# AT_LINK.net
KiCad netlist of a schematic drawn in Altium Designer
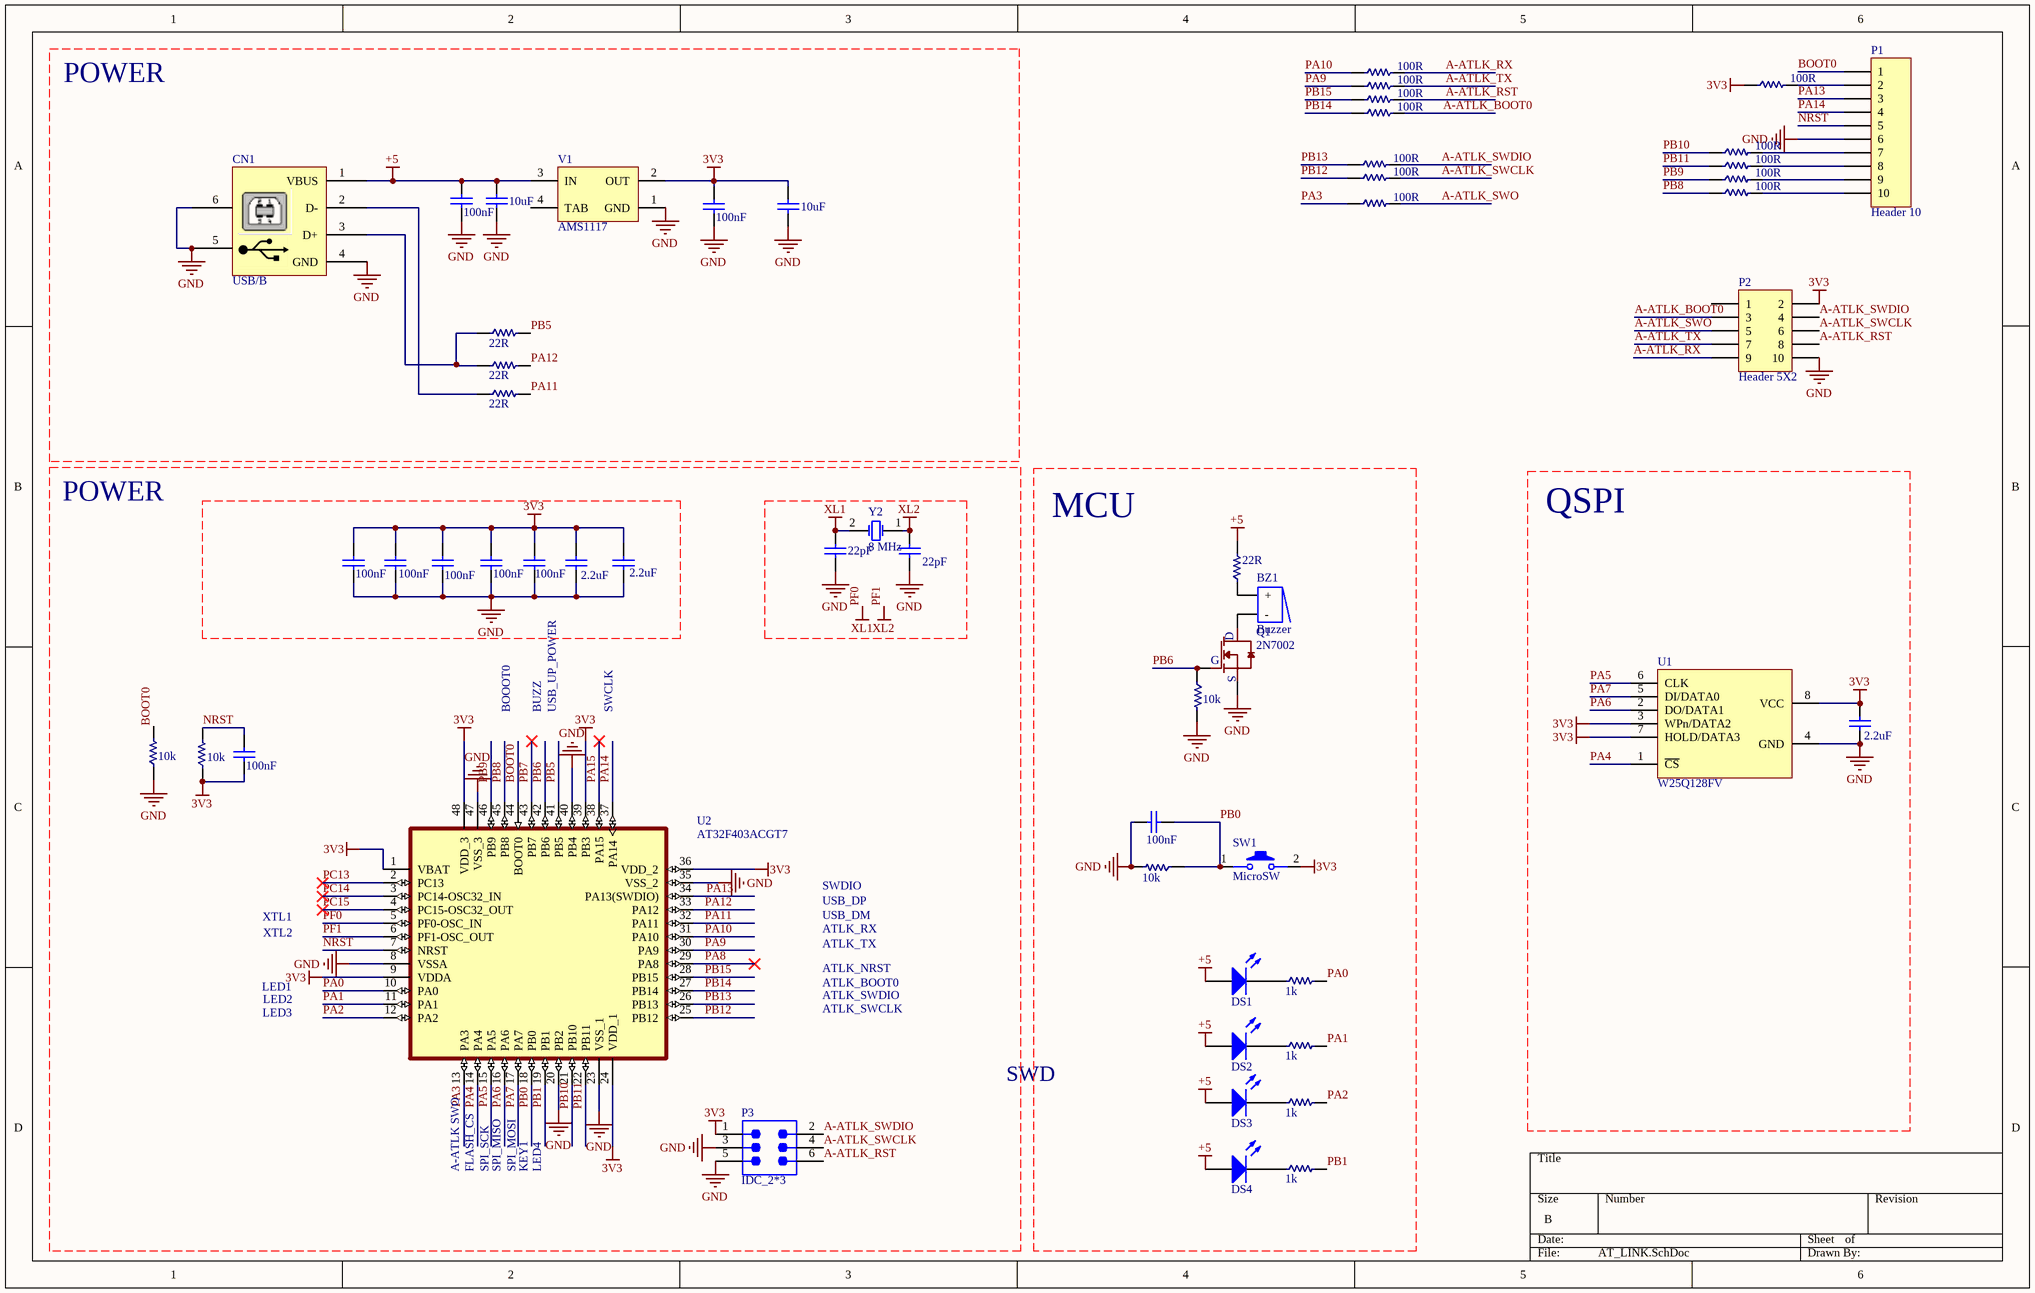
[diagram p0: AT_LINK.SchDoc]

(export (version "E")
  (design (tool "Eeschema 10.0.6"))
  (components
    (comp (ref "BZ1")
      (value "Buzzer")
      (footprint "Buzzer 3M")
      (fields (field (name "PART") "BUZZER 5V") (field (name "POWER") "CHINA"))
      (libsource (lib "NKH_Contacts") (part "Buzzer_small"))
    )
    (comp (ref "C1")
      (value "100nF")
      (footprint "CAP 0603")
      (description "cap_no_polar_seramic_multilayer")
      (fields (field (name "PART") "Cap-smd-0603-100nf"))
      (libsource (lib "R_C_D_T") (part "cap_no_polar_sig"))
    )
    (comp (ref "C2")
      (value "10uF")
      (footprint "CAP1206")
      (description "cap_no_polar_seramic_multilayer")
      (fields (field (name "PART") "Cap-smd-1206-10uf"))
      (libsource (lib "R_C_D_T") (part "cap_no_polar_sig"))
    )
    (comp (ref "C3")
      (value "100nF")
      (footprint "CAP 0603")
      (description "cap_no_polar_seramic_multilayer")
      (fields (field (name "PART") "Cap-smd-0603-100nf"))
      (libsource (lib "R_C_D_T") (part "cap_no_polar_sig"))
    )
    (comp (ref "C4")
      (value "10uF")
      (footprint "CAP1206")
      (description "cap_no_polar_seramic_multilayer")
      (fields (field (name "PART") "Cap-smd-1206-10uf"))
      (libsource (lib "R_C_D_T") (part "cap_no_polar_sig"))
    )
    (comp (ref "C5")
      (value "22pF")
      (footprint "CAP 0603")
      (description "cap_no_polar_seramic_multilayer")
      (fields (field (name "PART") "Cap-smd-0603-22pf"))
      (libsource (lib "R_C_D_T") (part "cap_no_polar_sig"))
    )
    (comp (ref "C6")
      (value "100nF")
      (footprint "CAP 0603")
      (description "cap_no_polar_seramic_multilayer")
      (fields (field (name "PART") "Cap-smd-0603-100nf"))
      (libsource (lib "R_C_D_T") (part "cap_no_polar_sig"))
    )
    (comp (ref "C7")
      (value "2.2uF")
      (footprint "CAP 0603")
      (description "cap_no_polar_seramic_multilayer")
      (fields (field (name "PART") "Cap-smd-0603-2.2uf"))
      (libsource (lib "R_C_D_T") (part "cap_no_polar_sig"))
    )
    (comp (ref "C8")
      (value "22pF")
      (footprint "CAP 0603")
      (description "cap_no_polar_seramic_multilayer")
      (fields (field (name "PART") "Cap-smd-0603-22pf"))
      (libsource (lib "R_C_D_T") (part "cap_no_polar_sig"))
    )
    (comp (ref "C9")
      (value "100nF")
      (footprint "CAP 0603")
      (description "cap_no_polar_seramic_multilayer")
      (fields (field (name "PART") "Cap-smd-0603-100nf"))
      (libsource (lib "R_C_D_T") (part "cap_no_polar_sig"))
    )
    (comp (ref "C10")
      (value "100nF")
      (footprint "CAP 0603")
      (description "cap_no_polar_seramic_multilayer")
      (fields (field (name "PART") "Cap-smd-0603-100nf"))
      (libsource (lib "R_C_D_T") (part "cap_no_polar_sig"))
    )
    (comp (ref "C11")
      (value "100nF")
      (footprint "CAP 0603")
      (description "cap_no_polar_seramic_multilayer")
      (fields (field (name "PART") "Cap-smd-0603-100nf"))
      (libsource (lib "R_C_D_T") (part "cap_no_polar_sig"))
    )
    (comp (ref "C12")
      (value "100nF")
      (footprint "CAP 0603")
      (description "cap_no_polar_seramic_multilayer")
      (fields (field (name "PART") "Cap-smd-0603-100nf"))
      (libsource (lib "R_C_D_T") (part "cap_no_polar_sig"))
    )
    (comp (ref "C13")
      (value "2.2uF")
      (footprint "CAP 0603")
      (description "cap_no_polar_seramic_multilayer")
      (fields (field (name "PART") "Cap-smd-0603-2.2uf"))
      (libsource (lib "R_C_D_T") (part "cap_no_polar_sig"))
    )
    (comp (ref "C14")
      (value "2.2uF")
      (footprint "CAP 0603")
      (description "cap_no_polar_seramic_multilayer")
      (fields (field (name "PART") "Cap-smd-0603-2.2uf"))
      (libsource (lib "R_C_D_T") (part "cap_no_polar_sig"))
    )
    (comp (ref "C15")
      (value "100nF")
      (footprint "CAP 0603")
      (description "cap_no_polar_seramic_multilayer")
      (fields (field (name "PART") "Cap-smd-0603-100nf"))
      (libsource (lib "R_C_D_T") (part "cap_no_polar_sig"))
    )
    (comp (ref "C16")
      (value "100nF")
      (footprint "CAP 0603")
      (description "cap_no_polar_seramic_multilayer")
      (fields (field (name "PART") "Cap-smd-0603-100nf"))
      (libsource (lib "R_C_D_T") (part "cap_no_polar_sig"))
    )
    (comp (ref "CN1")
      (value "USB/B")
      (footprint "USB_B")
      (description "USB Connector-B Type")
      (fields
        (field (name "PART") "USB_B")
        (field (name "POWER") "CHINA")
        (field (name "DESIGNER") "Eng. Saeid Jorablo")
      )
      (libsource (lib "NKH_Contacts") (part "USB_B"))
    )
    (comp (ref "DS1")
      (value "75 mW & 20 mA")
      (footprint "LED 0805 SMD")
      (fields (field (name "PART") "LED_0805_Red"))
      (libsource (lib "R_C_D_T") (part "LED"))
    )
    (comp (ref "DS2")
      (value "75 mW & 20 mA")
      (footprint "LED 0805 SMD")
      (fields (field (name "PART") "LED_0805_Red"))
      (libsource (lib "R_C_D_T") (part "LED"))
    )
    (comp (ref "DS3")
      (value "75 mW & 20 mA")
      (footprint "LED 0805 SMD")
      (fields (field (name "PART") "LED_0805_Red"))
      (libsource (lib "R_C_D_T") (part "LED"))
    )
    (comp (ref "DS4")
      (value "75 mW & 20 mA")
      (footprint "LED 0805 SMD")
      (fields (field (name "PART") "LED_0805_Red"))
      (libsource (lib "R_C_D_T") (part "LED"))
    )
    (comp (ref "P1")
      (value "Header 10")
      (footprint "HDR1X10")
      (description "Header, 10-Pin")
      (fields (field (name "PUBLISHER") "Altium Limited"))
      (libsource (lib "Miscellaneous Connectors") (part "Header 10"))
    )
    (comp (ref "P2")
      (value "Header 5X2")
      (footprint "HDR2X5")
      (description "Header, 5-Pin, Dual row")
      (fields (field (name "PUBLISHER") "Altium Limited"))
      (libsource (lib "Miscellaneous Connectors") (part "Header 5X2"))
    )
    (comp (ref "P3")
      (value "IDC_2*3")
      (footprint "HDB-6 right")
      (fields (field (name "PART") "HDB-2*3 Right"))
      (libsource (lib "NKH_Contacts") (part "IDC_2*3"))
    )
    (comp (ref "Q1")
      (value "2N7002")
      (footprint "SOT23_BEC_M")
      (fields (field (name "PART") "Mosfet-n-channel-2n7002"))
      (libsource (lib "R_C_D_T") (part "2N7002"))
    )
    (comp (ref "res1")
      (value "100R")
      (footprint "RES1206")
      (fields (field (name "PART") "resistor-smd-1206-100R") (field (name "DESIGNER") "rashid_behdarvand"))
      (libsource (lib "R_C_D_T") (part "resistor"))
    )
    (comp (ref "res2")
      (value "100R")
      (footprint "RES1206")
      (fields (field (name "PART") "resistor-smd-1206-100R") (field (name "DESIGNER") "rashid_behdarvand"))
      (libsource (lib "R_C_D_T") (part "resistor"))
    )
    (comp (ref "res3")
      (value "100R")
      (footprint "RES1206")
      (fields (field (name "PART") "resistor-smd-1206-100R") (field (name "DESIGNER") "rashid_behdarvand"))
      (libsource (lib "R_C_D_T") (part "resistor"))
    )
    (comp (ref "res4")
      (value "100R")
      (footprint "RES1206")
      (fields (field (name "PART") "resistor-smd-1206-100R") (field (name "DESIGNER") "rashid_behdarvand"))
      (libsource (lib "R_C_D_T") (part "resistor"))
    )
    (comp (ref "res5")
      (value "100R")
      (footprint "RES1206")
      (fields (field (name "PART") "resistor-smd-1206-100R") (field (name "DESIGNER") "rashid_behdarvand"))
      (libsource (lib "R_C_D_T") (part "resistor"))
    )
    (comp (ref "res6")
      (value "100R")
      (footprint "RES1206")
      (fields (field (name "PART") "resistor-smd-1206-100R") (field (name "DESIGNER") "rashid_behdarvand"))
      (libsource (lib "R_C_D_T") (part "resistor"))
    )
    (comp (ref "res7")
      (value "100R")
      (footprint "RES1206")
      (fields (field (name "PART") "resistor-smd-1206-100R") (field (name "DESIGNER") "rashid_behdarvand"))
      (libsource (lib "R_C_D_T") (part "resistor"))
    )
    (comp (ref "res8")
      (value "100R")
      (footprint "RES1206")
      (fields (field (name "PART") "resistor-smd-1206-100R") (field (name "DESIGNER") "rashid_behdarvand"))
      (libsource (lib "R_C_D_T") (part "resistor"))
    )
    (comp (ref "res9")
      (value "100R")
      (footprint "RES1206")
      (fields (field (name "PART") "resistor-smd-1206-100R") (field (name "DESIGNER") "rashid_behdarvand"))
      (libsource (lib "R_C_D_T") (part "resistor"))
    )
    (comp (ref "res10")
      (value "100R")
      (footprint "RES1206")
      (fields (field (name "PART") "resistor-smd-1206-100R") (field (name "DESIGNER") "rashid_behdarvand"))
      (libsource (lib "R_C_D_T") (part "resistor"))
    )
    (comp (ref "res11")
      (value "100R")
      (footprint "RES1206")
      (fields (field (name "PART") "resistor-smd-1206-100R") (field (name "DESIGNER") "rashid_behdarvand"))
      (libsource (lib "R_C_D_T") (part "resistor"))
    )
    (comp (ref "res12")
      (value "100R")
      (footprint "RES1206")
      (fields (field (name "PART") "resistor-smd-1206-100R") (field (name "DESIGNER") "rashid_behdarvand"))
      (libsource (lib "R_C_D_T") (part "resistor"))
    )
    (comp (ref "res14")
      (value "22R")
      (footprint "RES1206")
      (fields (field (name "PART") "resistor-smd-1206-22R") (field (name "DESIGNER") "rashid_behdarvand"))
      (libsource (lib "R_C_D_T") (part "resistor"))
    )
    (comp (ref "res15")
      (value "22R")
      (footprint "RES1206")
      (fields (field (name "PART") "resistor-smd-1206-22R") (field (name "DESIGNER") "rashid_behdarvand"))
      (libsource (lib "R_C_D_T") (part "resistor"))
    )
    (comp (ref "res16")
      (value "22R")
      (footprint "RES1206")
      (fields (field (name "PART") "resistor-smd-1206-22R") (field (name "DESIGNER") "rashid_behdarvand"))
      (libsource (lib "R_C_D_T") (part "resistor"))
    )
    (comp (ref "res17")
      (value "22R")
      (footprint "RES1206")
      (fields (field (name "PART") "resistor-smd-1206-22R") (field (name "DESIGNER") "rashid_behdarvand"))
      (libsource (lib "R_C_D_T") (part "resistor"))
    )
    (comp (ref "res18")
      (value "10k")
      (footprint "RES0603")
      (fields (field (name "PART") "resistor-smd-0603-10k") (field (name "DESIGNER") "rashid_behdarvand"))
      (libsource (lib "R_C_D_T") (part "resistor"))
    )
    (comp (ref "res19")
      (value "10k")
      (footprint "RES0603")
      (fields (field (name "PART") "resistor-smd-0603-10k") (field (name "DESIGNER") "rashid_behdarvand"))
      (libsource (lib "R_C_D_T") (part "resistor"))
    )
    (comp (ref "res20")
      (value "10k")
      (footprint "RES0603")
      (fields (field (name "PART") "resistor-smd-0603-10k") (field (name "DESIGNER") "rashid_behdarvand"))
      (libsource (lib "R_C_D_T") (part "resistor"))
    )
    (comp (ref "res21")
      (value "10k")
      (footprint "RES0603")
      (fields (field (name "PART") "resistor-smd-0603-10k") (field (name "DESIGNER") "rashid_behdarvand"))
      (libsource (lib "R_C_D_T") (part "resistor"))
    )
    (comp (ref "res22")
      (value "1k")
      (footprint "RES1206")
      (fields (field (name "PART") "resistor-smd-1206-1k") (field (name "DESIGNER") "rashid_behdarvand"))
      (libsource (lib "R_C_D_T") (part "resistor"))
    )
    (comp (ref "res23")
      (value "1k")
      (footprint "RES1206")
      (fields (field (name "PART") "resistor-smd-1206-1k") (field (name "DESIGNER") "rashid_behdarvand"))
      (libsource (lib "R_C_D_T") (part "resistor"))
    )
    (comp (ref "res24")
      (value "1k")
      (footprint "RES1206")
      (fields (field (name "PART") "resistor-smd-1206-1k") (field (name "DESIGNER") "rashid_behdarvand"))
      (libsource (lib "R_C_D_T") (part "resistor"))
    )
    (comp (ref "res25")
      (value "1k")
      (footprint "RES1206")
      (fields (field (name "PART") "resistor-smd-1206-1k") (field (name "DESIGNER") "rashid_behdarvand"))
      (libsource (lib "R_C_D_T") (part "resistor"))
    )
    (comp (ref "SW1")
      (value "MicroSW")
      (footprint "SW-Tactile-SMD")
      (fields (field (name "PART") "MicroSW_SMD_2Pin"))
      (libsource (lib "NKH_Contacts") (part "MicroSW"))
    )
    (comp (ref "U1") (value "W25Q128FV") (footprint "SOIC-8W") (libsource (lib "NKH_IC") (part "W25Q128FV")))
    (comp (ref "U2")
      (value "AT32F403ACGT7")
      (footprint "LQFP48_N")
      (libsource (lib "NKH_IC") (part "AT32F403ACGT7"))
    )
    (comp (ref "V1")
      (value "AMS1117")
      (footprint "MP04A_N")
      (description "x.x Volt, 800mA Low-Dropout Linear Regulator, 4-pin SOT-223")
      (fields
        (field (name "PARTNUMBER") "LM1117IMP-3.3")
        (field (name "MANUFACTURER") "National Semiconductor")
        (field (name "PUBLISHER") "Altium Limited")
      )
      (libsource (lib "NKH_IC") (part "LM1117IMP-x.x"))
    )
    (comp (ref "Y2")
      (value "8 MHz")
      (footprint "Crystal DIP")
      (description "XTAL Crystal")
      (fields (field (name "PART") "Crystal SMD - 8MHZ") (field (name "Comment") "8MHZ"))
      (libsource (lib "R_C_D_T") (part "XTAL"))
    )
  )
  (nets
    (net (code "1") (name "+5") (class "Default")
      (node (ref "C1") (pin "2") (pinfunction "2_2") (pintype "passive"))
      (node (ref "C2") (pin "2") (pinfunction "2_2") (pintype "passive"))
      (node (ref "CN1") (pin "1") (pinfunction "VBUS_1") (pintype "power_in"))
      (node (ref "DS1") (pin "1") (pinfunction "A_1") (pintype "passive"))
      (node (ref "DS2") (pin "1") (pinfunction "A_1") (pintype "passive"))
      (node (ref "DS3") (pin "1") (pinfunction "A_1") (pintype "passive"))
      (node (ref "DS4") (pin "1") (pinfunction "A_1") (pintype "passive"))
      (node (ref "V1") (pin "3") (pinfunction "IN_3") (pintype "power_in"))
      (node (ref "res17") (pin "2") (pinfunction "2_2") (pintype "passive"))
    )
    (net (code "2") (name "/A-ATLK_BOOT0") (class "Default")
      (node (ref "P2") (pin "3") (pinfunction "3_3") (pintype "passive"))
      (node (ref "res5") (pin "2") (pinfunction "2_2") (pintype "passive"))
    )
    (net (code "3") (name "/A-ATLK_RST") (class "Default")
      (node (ref "P2") (pin "8") (pinfunction "8_8") (pintype "passive"))
      (node (ref "P3") (pin "6") (pinfunction "6_6") (pintype "passive"))
      (node (ref "res4") (pin "2") (pinfunction "2_2") (pintype "passive"))
    )
    (net (code "4") (name "/A-ATLK_RX") (class "Default")
      (node (ref "P2") (pin "9") (pinfunction "9_9") (pintype "passive"))
      (node (ref "res1") (pin "2") (pinfunction "2_2") (pintype "passive"))
    )
    (net (code "5") (name "/A-ATLK_SWCLK") (class "Default")
      (node (ref "P2") (pin "6") (pinfunction "6_6") (pintype "passive"))
      (node (ref "P3") (pin "4") (pinfunction "4_4") (pintype "passive"))
      (node (ref "res9") (pin "2") (pinfunction "2_2") (pintype "passive"))
    )
    (net (code "6") (name "/A-ATLK_SWDIO") (class "Default")
      (node (ref "P2") (pin "4") (pinfunction "4_4") (pintype "passive"))
      (node (ref "P3") (pin "2") (pinfunction "2_2") (pintype "passive"))
      (node (ref "res7") (pin "2") (pinfunction "2_2") (pintype "passive"))
    )
    (net (code "7") (name "/A-ATLK_SWO") (class "Default")
      (node (ref "P2") (pin "5") (pinfunction "5_5") (pintype "passive"))
      (node (ref "res12") (pin "2") (pinfunction "2_2") (pintype "passive"))
    )
    (net (code "8") (name "/A-ATLK_TX") (class "Default")
      (node (ref "P2") (pin "7") (pinfunction "7_7") (pintype "passive"))
      (node (ref "res2") (pin "2") (pinfunction "2_2") (pintype "passive"))
    )
    (net (code "9") (name "/BOOT0") (class "Default")
      (node (ref "P1") (pin "1") (pinfunction "1_1") (pintype "passive"))
      (node (ref "U2") (pin "44") (pinfunction "BOOT0_44") (pintype "input"))
      (node (ref "res19") (pin "2") (pinfunction "2_2") (pintype "passive"))
    )
    (net (code "10") (name "/NRST") (class "Default")
      (node (ref "C15") (pin "2") (pinfunction "2_2") (pintype "passive"))
      (node (ref "P1") (pin "5") (pinfunction "5_5") (pintype "passive"))
      (node (ref "U2") (pin "7") (pinfunction "NRST_7") (pintype "bidirectional"))
      (node (ref "res20") (pin "2") (pinfunction "2_2") (pintype "passive"))
    )
    (net (code "11") (name "/PA0") (class "Default")
      (node (ref "U2") (pin "10") (pinfunction "PA0_10") (pintype "bidirectional"))
      (node (ref "res22") (pin "2") (pinfunction "2_2") (pintype "passive"))
    )
    (net (code "12") (name "/PA1") (class "Default")
      (node (ref "U2") (pin "11") (pinfunction "PA1_11") (pintype "bidirectional"))
      (node (ref "res23") (pin "2") (pinfunction "2_2") (pintype "passive"))
    )
    (net (code "13") (name "/PA2") (class "Default")
      (node (ref "U2") (pin "12") (pinfunction "PA2_12") (pintype "bidirectional"))
      (node (ref "res24") (pin "2") (pinfunction "2_2") (pintype "passive"))
    )
    (net (code "14") (name "/PA3") (class "Default")
      (node (ref "U2") (pin "13") (pinfunction "PA3_13") (pintype "bidirectional"))
      (node (ref "res12") (pin "1") (pinfunction "1_1") (pintype "passive"))
    )
    (net (code "15") (name "/PA4") (class "Default")
      (node (ref "U1") (pin "1") (pinfunction "~{CS}_1") (pintype "passive"))
      (node (ref "U2") (pin "14") (pinfunction "PA4_14") (pintype "bidirectional"))
    )
    (net (code "16") (name "/PA5") (class "Default")
      (node (ref "U1") (pin "6") (pinfunction "CLK_6") (pintype "passive"))
      (node (ref "U2") (pin "15") (pinfunction "PA5_15") (pintype "bidirectional"))
    )
    (net (code "17") (name "/PA6") (class "Default")
      (node (ref "U1") (pin "2") (pinfunction "DO/DATA1_2") (pintype "passive"))
      (node (ref "U2") (pin "16") (pinfunction "PA6_16") (pintype "bidirectional"))
    )
    (net (code "18") (name "/PA7") (class "Default")
      (node (ref "U1") (pin "5") (pinfunction "DI/DATA0_5") (pintype "passive"))
      (node (ref "U2") (pin "17") (pinfunction "PA7_17") (pintype "bidirectional"))
    )
    (net (code "19") (name "/PA8") (class "Default")
      (node (ref "U2") (pin "29") (pinfunction "PA8_29") (pintype "bidirectional+no_connect"))
    )
    (net (code "20") (name "/PA9") (class "Default")
      (node (ref "U2") (pin "30") (pinfunction "PA9_30") (pintype "bidirectional"))
      (node (ref "res2") (pin "1") (pinfunction "1_1") (pintype "passive"))
    )
    (net (code "21") (name "/PA10") (class "Default")
      (node (ref "U2") (pin "31") (pinfunction "PA10_31") (pintype "bidirectional"))
      (node (ref "res1") (pin "1") (pinfunction "1_1") (pintype "passive"))
    )
    (net (code "22") (name "/PA11") (class "Default")
      (node (ref "U2") (pin "32") (pinfunction "PA11_32") (pintype "bidirectional"))
      (node (ref "res16") (pin "2") (pinfunction "2_2") (pintype "passive"))
    )
    (net (code "23") (name "/PA12") (class "Default")
      (node (ref "U2") (pin "33") (pinfunction "PA12_33") (pintype "bidirectional"))
      (node (ref "res15") (pin "2") (pinfunction "2_2") (pintype "passive"))
    )
    (net (code "24") (name "/PA13") (class "Default")
      (node (ref "P1") (pin "3") (pinfunction "3_3") (pintype "passive"))
      (node (ref "U2") (pin "34") (pinfunction "PA13(SWDIO)_34") (pintype "bidirectional"))
    )
    (net (code "25") (name "/PA14") (class "Default")
      (node (ref "P1") (pin "4") (pinfunction "4_4") (pintype "passive"))
      (node (ref "U2") (pin "37") (pinfunction "PA14_37") (pintype "bidirectional"))
    )
    (net (code "26") (name "/PA15") (class "Default")
      (node (ref "U2") (pin "38") (pinfunction "PA15_38") (pintype "bidirectional+no_connect"))
    )
    (net (code "27") (name "/PB0") (class "Default")
      (node (ref "C16") (pin "1") (pinfunction "1_1") (pintype "passive"))
      (node (ref "SW1") (pin "1") (pinfunction "Button_1") (pintype "passive"))
      (node (ref "U2") (pin "18") (pinfunction "PB0_18") (pintype "bidirectional"))
      (node (ref "res21") (pin "1") (pinfunction "1_1") (pintype "passive"))
    )
    (net (code "28") (name "/PB1") (class "Default")
      (node (ref "U2") (pin "19") (pinfunction "PB1_19") (pintype "bidirectional"))
      (node (ref "res25") (pin "2") (pinfunction "2_2") (pintype "passive"))
    )
    (net (code "29") (name "/PB5") (class "Default")
      (node (ref "U2") (pin "41") (pinfunction "PB5_41") (pintype "bidirectional"))
      (node (ref "res14") (pin "2") (pinfunction "2_2") (pintype "passive"))
    )
    (net (code "30") (name "/PB6") (class "Default")
      (node (ref "Q1") (pin "1") (pinfunction "G_1") (pintype "passive"))
      (node (ref "U2") (pin "42") (pinfunction "PB6_42") (pintype "bidirectional"))
      (node (ref "res18") (pin "1") (pinfunction "1_1") (pintype "passive"))
    )
    (net (code "31") (name "/PB7") (class "Default")
      (node (ref "U2") (pin "43") (pinfunction "PB7_43") (pintype "bidirectional+no_connect"))
    )
    (net (code "32") (name "/PB8") (class "Default")
      (node (ref "U2") (pin "45") (pinfunction "PB8_45") (pintype "bidirectional"))
      (node (ref "res11") (pin "1") (pinfunction "1_1") (pintype "passive"))
    )
    (net (code "33") (name "/PB9") (class "Default")
      (node (ref "U2") (pin "46") (pinfunction "PB9_46") (pintype "bidirectional"))
      (node (ref "res10") (pin "1") (pinfunction "1_1") (pintype "passive"))
    )
    (net (code "34") (name "/PB10") (class "Default")
      (node (ref "U2") (pin "21") (pinfunction "PB10_21") (pintype "bidirectional"))
      (node (ref "res6") (pin "1") (pinfunction "1_1") (pintype "passive"))
    )
    (net (code "35") (name "/PB11") (class "Default")
      (node (ref "U2") (pin "22") (pinfunction "PB11_22") (pintype "bidirectional"))
      (node (ref "res8") (pin "1") (pinfunction "1_1") (pintype "passive"))
    )
    (net (code "36") (name "/PB12") (class "Default")
      (node (ref "U2") (pin "25") (pinfunction "PB12_25") (pintype "bidirectional"))
      (node (ref "res9") (pin "1") (pinfunction "1_1") (pintype "passive"))
    )
    (net (code "37") (name "/PB13") (class "Default")
      (node (ref "U2") (pin "26") (pinfunction "PB13_26") (pintype "bidirectional"))
      (node (ref "res7") (pin "1") (pinfunction "1_1") (pintype "passive"))
    )
    (net (code "38") (name "/PB14") (class "Default")
      (node (ref "U2") (pin "27") (pinfunction "PB14_27") (pintype "bidirectional"))
      (node (ref "res5") (pin "1") (pinfunction "1_1") (pintype "passive"))
    )
    (net (code "39") (name "/PB15") (class "Default")
      (node (ref "U2") (pin "28") (pinfunction "PB15_28") (pintype "bidirectional"))
      (node (ref "res4") (pin "1") (pinfunction "1_1") (pintype "passive"))
    )
    (net (code "40") (name "/PC13") (class "Default")
      (node (ref "U2") (pin "2") (pinfunction "PC13_2") (pintype "bidirectional+no_connect"))
    )
    (net (code "41") (name "/PC14") (class "Default")
      (node (ref "U2") (pin "3") (pinfunction "PC14-OSC32_IN_3") (pintype "bidirectional+no_connect"))
    )
    (net (code "42") (name "/PC15") (class "Default")
      (node (ref "U2") (pin "4") (pinfunction "PC15-OSC32_OUT_4") (pintype "bidirectional+no_connect"))
    )
    (net (code "43") (name "3V3") (class "Default")
      (node (ref "C10") (pin "2") (pinfunction "2_2") (pintype "passive"))
      (node (ref "C11") (pin "2") (pinfunction "2_2") (pintype "passive"))
      (node (ref "C12") (pin "2") (pinfunction "2_2") (pintype "passive"))
      (node (ref "C13") (pin "2") (pinfunction "2_2") (pintype "passive"))
      (node (ref "C14") (pin "2") (pinfunction "2_2") (pintype "passive"))
      (node (ref "C15") (pin "1") (pinfunction "1_1") (pintype "passive"))
      (node (ref "C3") (pin "2") (pinfunction "2_2") (pintype "passive"))
      (node (ref "C4") (pin "2") (pinfunction "2_2") (pintype "passive"))
      (node (ref "C6") (pin "2") (pinfunction "2_2") (pintype "passive"))
      (node (ref "C7") (pin "2") (pinfunction "2_2") (pintype "passive"))
      (node (ref "C9") (pin "2") (pinfunction "2_2") (pintype "passive"))
      (node (ref "P2") (pin "2") (pinfunction "2_2") (pintype "passive"))
      (node (ref "P3") (pin "1") (pinfunction "1_1") (pintype "passive"))
      (node (ref "SW1") (pin "2") (pinfunction "2_2") (pintype "passive"))
      (node (ref "U1") (pin "3") (pinfunction "WPn/DATA2_3") (pintype "passive"))
      (node (ref "U1") (pin "7") (pinfunction "HOLD/DATA3_7") (pintype "passive"))
      (node (ref "U1") (pin "8") (pinfunction "VCC_8") (pintype "passive"))
      (node (ref "U2") (pin "1") (pinfunction "VBAT_1") (pintype "power_in"))
      (node (ref "U2") (pin "24") (pinfunction "VDD_1_24") (pintype "power_in"))
      (node (ref "U2") (pin "36") (pinfunction "VDD_2_36") (pintype "bidirectional"))
      (node (ref "U2") (pin "39") (pinfunction "PB3_39") (pintype "bidirectional"))
      (node (ref "U2") (pin "48") (pinfunction "VDD_3_48") (pintype "power_in"))
      (node (ref "U2") (pin "9") (pinfunction "VDDA_9") (pintype "power_in"))
      (node (ref "V1") (pin "2") (pinfunction "OUT_2") (pintype "power_in"))
      (node (ref "res20") (pin "1") (pinfunction "1_1") (pintype "passive"))
      (node (ref "res3") (pin "1") (pinfunction "1_1") (pintype "passive"))
    )
    (net (code "44") (name "GND") (class "Default")
      (node (ref "C1") (pin "1") (pinfunction "1_1") (pintype "passive"))
      (node (ref "C10") (pin "1") (pinfunction "1_1") (pintype "passive"))
      (node (ref "C11") (pin "1") (pinfunction "1_1") (pintype "passive"))
      (node (ref "C12") (pin "1") (pinfunction "1_1") (pintype "passive"))
      (node (ref "C13") (pin "1") (pinfunction "1_1") (pintype "passive"))
      (node (ref "C14") (pin "1") (pinfunction "1_1") (pintype "passive"))
      (node (ref "C16") (pin "2") (pinfunction "2_2") (pintype "passive"))
      (node (ref "C2") (pin "1") (pinfunction "1_1") (pintype "passive"))
      (node (ref "C3") (pin "1") (pinfunction "1_1") (pintype "passive"))
      (node (ref "C4") (pin "1") (pinfunction "1_1") (pintype "passive"))
      (node (ref "C5") (pin "1") (pinfunction "1_1") (pintype "passive"))
      (node (ref "C6") (pin "1") (pinfunction "1_1") (pintype "passive"))
      (node (ref "C7") (pin "1") (pinfunction "1_1") (pintype "passive"))
      (node (ref "C8") (pin "2") (pinfunction "2_2") (pintype "passive"))
      (node (ref "C9") (pin "1") (pinfunction "1_1") (pintype "passive"))
      (node (ref "CN1") (pin "4") (pinfunction "GND_4") (pintype "power_in"))
      (node (ref "CN1") (pin "5") (pinfunction "6_5") (pintype "power_in"))
      (node (ref "CN1") (pin "6") (pinfunction "6_6") (pintype "power_in"))
      (node (ref "P1") (pin "6") (pinfunction "6_6") (pintype "passive"))
      (node (ref "P2") (pin "10") (pinfunction "10_10") (pintype "passive"))
      (node (ref "P3") (pin "3") (pinfunction "3_3") (pintype "passive"))
      (node (ref "P3") (pin "5") (pinfunction "5_5") (pintype "passive"))
      (node (ref "Q1") (pin "2") (pinfunction "S_2") (pintype "passive"))
      (node (ref "U1") (pin "4") (pinfunction "GND_4") (pintype "passive"))
      (node (ref "U2") (pin "20") (pinfunction "PB2_20") (pintype "bidirectional"))
      (node (ref "U2") (pin "23") (pinfunction "VSS_1_23") (pintype "power_in"))
      (node (ref "U2") (pin "35") (pinfunction "VSS_2_35") (pintype "bidirectional"))
      (node (ref "U2") (pin "40") (pinfunction "PB4_40") (pintype "bidirectional"))
      (node (ref "U2") (pin "47") (pinfunction "VSS_3_47") (pintype "power_in"))
      (node (ref "U2") (pin "8") (pinfunction "VSSA_8") (pintype "power_in"))
      (node (ref "V1") (pin "1") (pinfunction "GND_1") (pintype "power_in"))
      (node (ref "res18") (pin "2") (pinfunction "2_2") (pintype "passive"))
      (node (ref "res19") (pin "1") (pinfunction "1_1") (pintype "passive"))
      (node (ref "res21") (pin "2") (pinfunction "2_2") (pintype "passive"))
    )
    (net (code "45") (name "Net-(BZ1-+)") (class "Default")
      (node (ref "BZ1") (pin "1") (pinfunction "+_1") (pintype "passive"))
      (node (ref "res17") (pin "1") (pinfunction "1_1") (pintype "passive"))
    )
    (net (code "46") (name "Net-(BZ1--)") (class "Default")
      (node (ref "BZ1") (pin "2") (pinfunction "-_2") (pintype "passive"))
      (node (ref "Q1") (pin "3") (pinfunction "D_3") (pintype "passive"))
    )
    (net (code "47") (name "Net-(CN1-D+)") (class "Default")
      (node (ref "CN1") (pin "3") (pinfunction "D+_3") (pintype "passive"))
      (node (ref "res14") (pin "1") (pinfunction "1_1") (pintype "passive"))
      (node (ref "res15") (pin "1") (pinfunction "1_1") (pintype "passive"))
    )
    (net (code "48") (name "Net-(CN1-D-)") (class "Default")
      (node (ref "CN1") (pin "2") (pinfunction "D-_2") (pintype "passive"))
      (node (ref "res16") (pin "1") (pinfunction "1_1") (pintype "passive"))
    )
    (net (code "49") (name "Net-(DS1-K)") (class "Default")
      (node (ref "DS1") (pin "2") (pinfunction "K_2") (pintype "passive"))
      (node (ref "res22") (pin "1") (pinfunction "1_1") (pintype "passive"))
    )
    (net (code "50") (name "Net-(DS2-K)") (class "Default")
      (node (ref "DS2") (pin "2") (pinfunction "K_2") (pintype "passive"))
      (node (ref "res23") (pin "1") (pinfunction "1_1") (pintype "passive"))
    )
    (net (code "51") (name "Net-(DS3-K)") (class "Default")
      (node (ref "DS3") (pin "2") (pinfunction "K_2") (pintype "passive"))
      (node (ref "res24") (pin "1") (pinfunction "1_1") (pintype "passive"))
    )
    (net (code "52") (name "Net-(DS4-K)") (class "Default")
      (node (ref "DS4") (pin "2") (pinfunction "K_2") (pintype "passive"))
      (node (ref "res25") (pin "1") (pinfunction "1_1") (pintype "passive"))
    )
    (net (code "53") (name "Net-(P1-Pad2)") (class "Default")
      (node (ref "P1") (pin "2") (pinfunction "2_2") (pintype "passive"))
      (node (ref "res3") (pin "2") (pinfunction "2_2") (pintype "passive"))
    )
    (net (code "54") (name "Net-(P1-Pad7)") (class "Default")
      (node (ref "P1") (pin "7") (pinfunction "7_7") (pintype "passive"))
      (node (ref "res6") (pin "2") (pinfunction "2_2") (pintype "passive"))
    )
    (net (code "55") (name "Net-(P1-Pad8)") (class "Default")
      (node (ref "P1") (pin "8") (pinfunction "8_8") (pintype "passive"))
      (node (ref "res8") (pin "2") (pinfunction "2_2") (pintype "passive"))
    )
    (net (code "56") (name "Net-(P1-Pad9)") (class "Default")
      (node (ref "P1") (pin "9") (pinfunction "9_9") (pintype "passive"))
      (node (ref "res10") (pin "2") (pinfunction "2_2") (pintype "passive"))
    )
    (net (code "57") (name "Net-(P1-Pad10)") (class "Default")
      (node (ref "P1") (pin "10") (pinfunction "10_10") (pintype "passive"))
      (node (ref "res11") (pin "2") (pinfunction "2_2") (pintype "passive"))
    )
    (net (code "58") (name "XL1") (class "Default")
      (node (ref "C5") (pin "2") (pinfunction "2_2") (pintype "passive"))
      (node (ref "U2") (pin "5") (pinfunction "PF0-OSC_IN_5") (pintype "bidirectional"))
      (node (ref "Y2") (pin "2") (pinfunction "OSC2_2") (pintype "passive"))
    )
    (net (code "59") (name "XL2") (class "Default")
      (node (ref "C8") (pin "1") (pinfunction "1_1") (pintype "passive"))
      (node (ref "U2") (pin "6") (pinfunction "PF1-OSC_OUT_6") (pintype "bidirectional"))
      (node (ref "Y2") (pin "1") (pinfunction "OSC1_1") (pintype "passive"))
    )
    (net (code "60") (name "unconnected-(P2-Pad1)") (class "Default")
      (node (ref "P2") (pin "1") (pinfunction "1_1") (pintype "passive"))
    )
    (net (code "61") (name "unconnected-(V1-TAB-Pad4)") (class "Default")
      (node (ref "V1") (pin "4") (pinfunction "TAB_4") (pintype "power_in"))
    )
  )
)
